# axiom_beta_interface_dummy_v0_13_r1_2.net
KiCad netlist of a schematic drawn in EAGLE
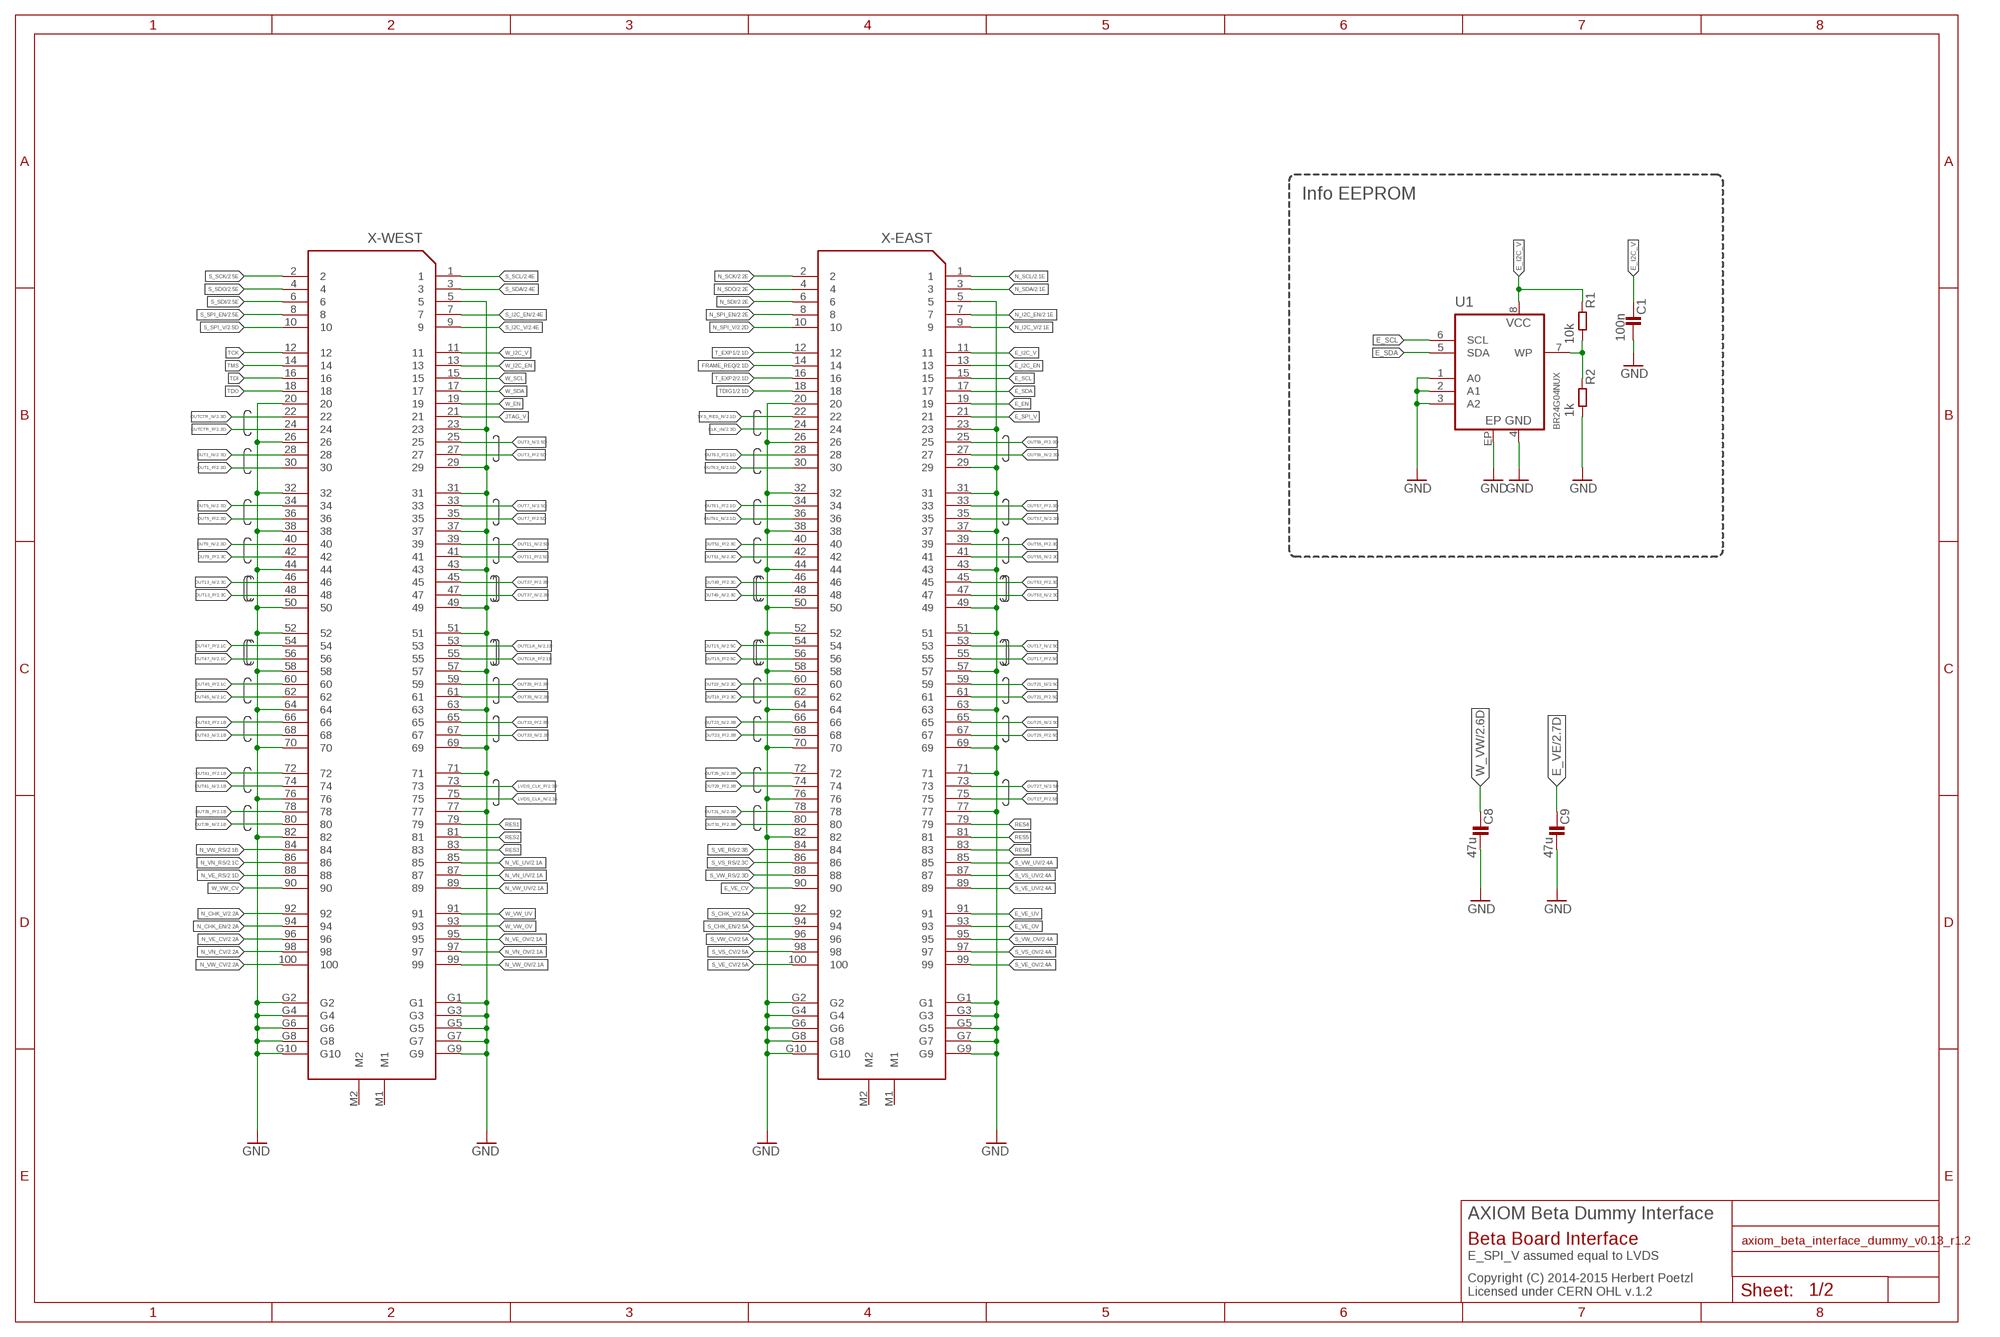
[diagram p0: schematic, sheet 1]
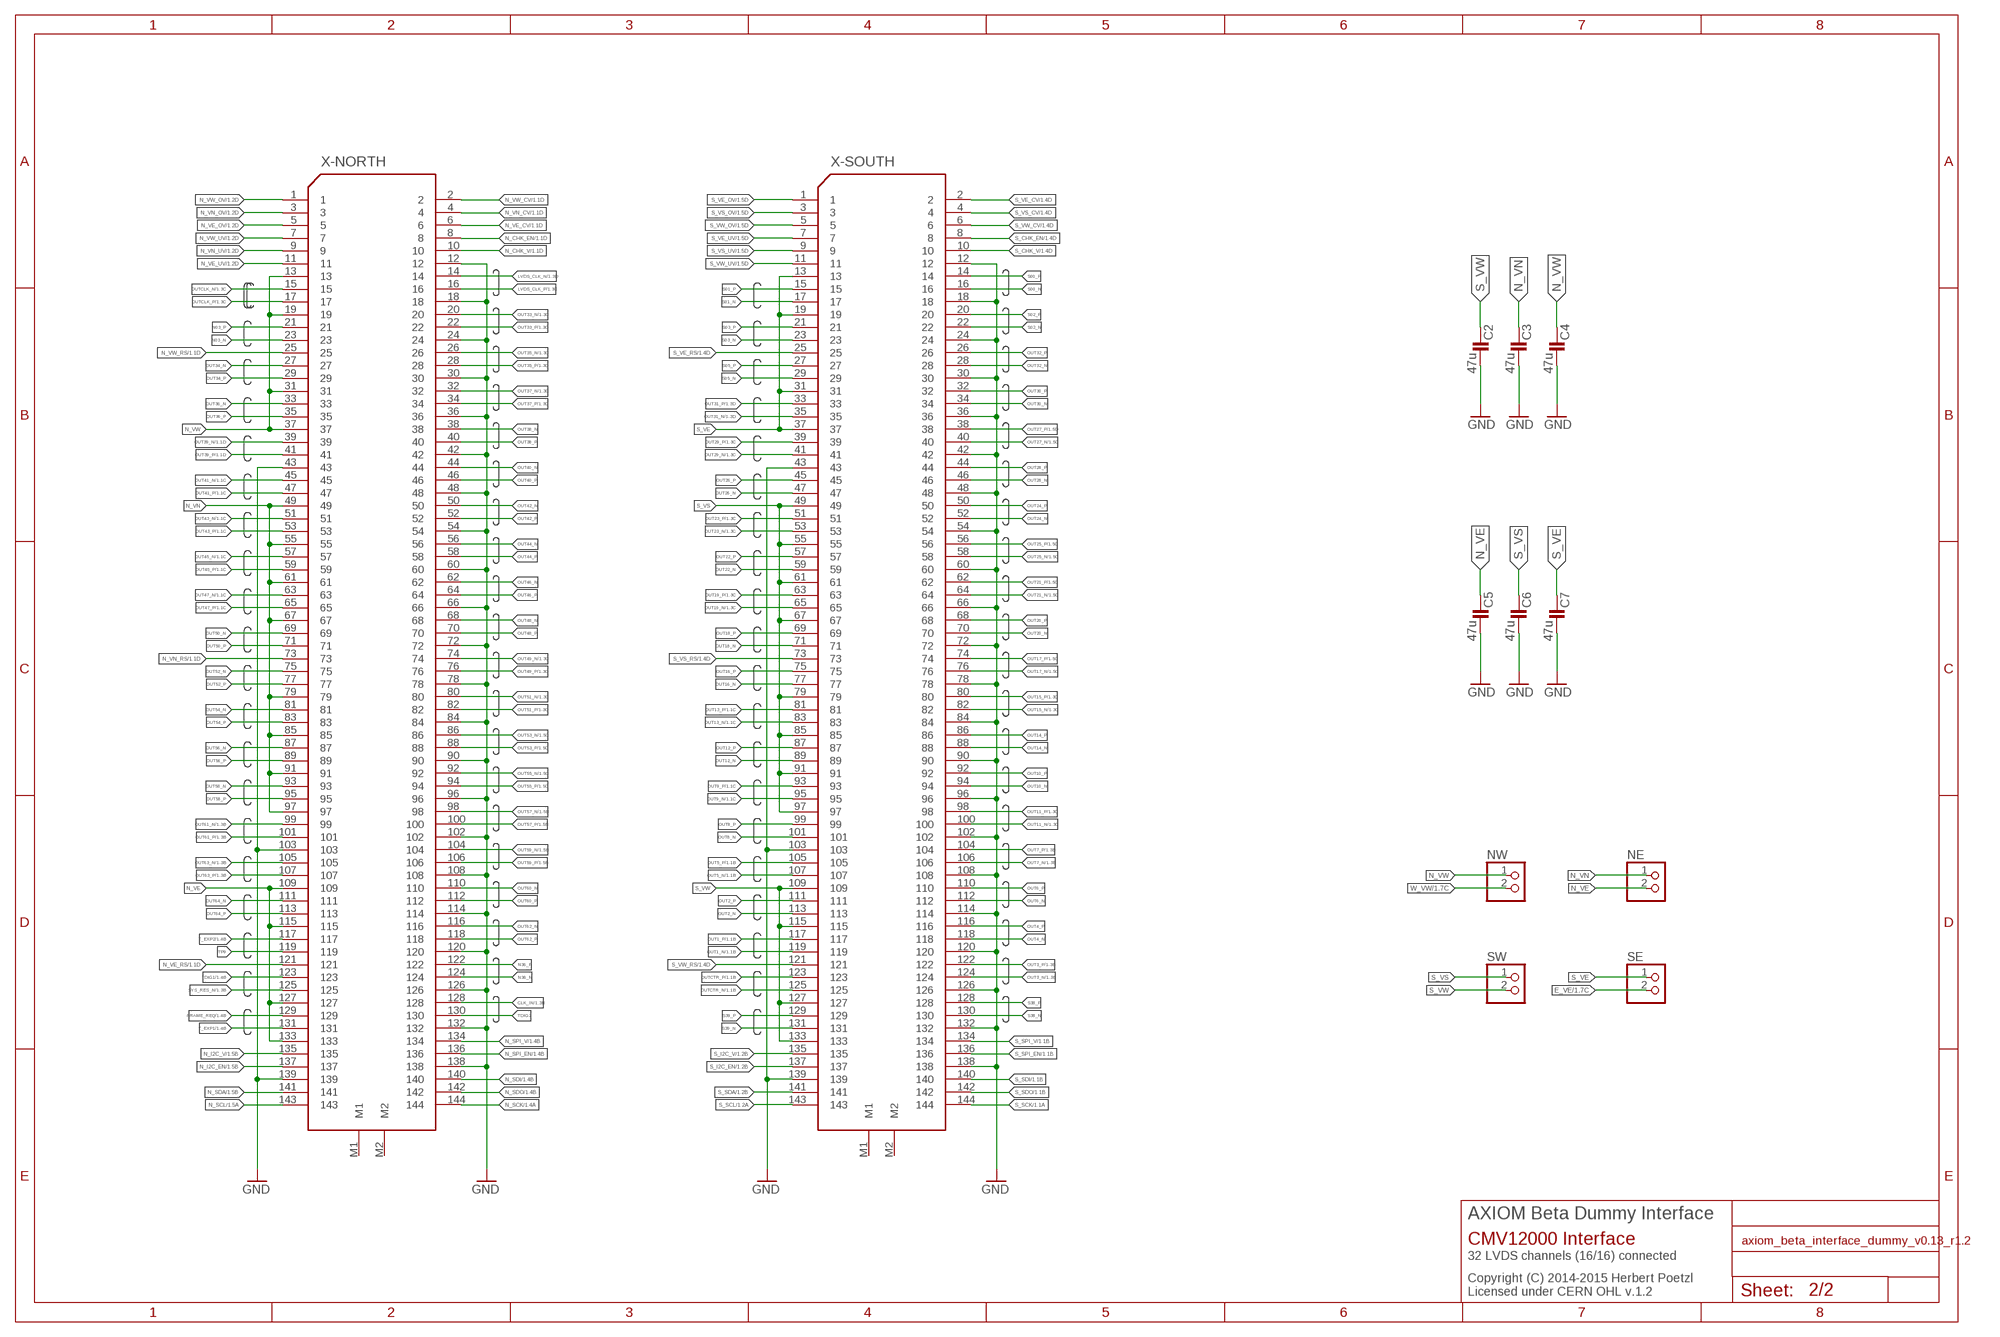
[diagram p1: schematic, sheet 2]

(export (version "E")
  (design (tool "Eeschema 10.0.6"))
  (components
    (comp (ref "C1")
      (value "100n")
      (footprint "eagle-import:0402-B")
      (libsource (lib "eagle-import") (part "C0402-B"))
    )
    (comp (ref "C8")
      (value "47u")
      (footprint "eagle-import:0805-B")
      (libsource (lib "eagle-import") (part "C0805-B"))
    )
    (comp (ref "C9")
      (value "47u")
      (footprint "eagle-import:0805-B")
      (libsource (lib "eagle-import") (part "C0805-B"))
    )
    (comp (ref "R1")
      (value "10k")
      (footprint "eagle-import:0402-B")
      (libsource (lib "eagle-import") (part "R0402-B"))
    )
    (comp (ref "R2")
      (value "1k")
      (footprint "eagle-import:0402-B")
      (libsource (lib "eagle-import") (part "R0402-B"))
    )
    (comp (ref "U1")
      (value "BR24G04NUX")
      (footprint "eagle-import:DFN200X300X100-9N")
      (libsource (lib "eagle-import") (part "BR24G04NUX"))
    )
    (comp (ref "X-EAST")
      (value "FX10-100/10P")
      (footprint "eagle-import:FX10A-100P_10")
      (libsource (lib "eagle-import") (part "FX10-100/10P"))
    )
    (comp (ref "X-WEST")
      (value "FX10-100/10P")
      (footprint "eagle-import:FX10A-100P_10")
      (libsource (lib "eagle-import") (part "FX10-100/10P"))
    )
    (comp (ref "C2")
      (value "47u")
      (footprint "eagle-import:0805-B")
      (libsource (lib "eagle-import") (part "C0805-B"))
    )
    (comp (ref "C3")
      (value "47u")
      (footprint "eagle-import:0805-B")
      (libsource (lib "eagle-import") (part "C0805-B"))
    )
    (comp (ref "C4")
      (value "47u")
      (footprint "eagle-import:0805-B")
      (libsource (lib "eagle-import") (part "C0805-B"))
    )
    (comp (ref "C5")
      (value "47u")
      (footprint "eagle-import:0805-B")
      (libsource (lib "eagle-import") (part "C0805-B"))
    )
    (comp (ref "C6")
      (value "47u")
      (footprint "eagle-import:0805-B")
      (libsource (lib "eagle-import") (part "C0805-B"))
    )
    (comp (ref "C7")
      (value "47u")
      (footprint "eagle-import:0805-B")
      (libsource (lib "eagle-import") (part "C0805-B"))
    )
    (comp (ref "NE")
      (value "PINHD-1X02_2.54")
      (footprint "eagle-import:1X02")
      (libsource (lib "eagle-import") (part "PINHD-1X02_2.54"))
    )
    (comp (ref "NW")
      (value "PINHD-1X02_2.54")
      (footprint "eagle-import:1X02")
      (libsource (lib "eagle-import") (part "PINHD-1X02_2.54"))
    )
    (comp (ref "SE")
      (value "PINHD-1X02_2.54")
      (footprint "eagle-import:1X02")
      (libsource (lib "eagle-import") (part "PINHD-1X02_2.54"))
    )
    (comp (ref "SW")
      (value "PINHD-1X02_2.54")
      (footprint "eagle-import:1X02")
      (libsource (lib "eagle-import") (part "PINHD-1X02_2.54"))
    )
    (comp (ref "X-NORTH")
      (value "FX10-144S")
      (footprint "eagle-import:FX10A-144S")
      (libsource (lib "eagle-import") (part "FX10-144S"))
    )
    (comp (ref "X-SOUTH")
      (value "FX10-144S")
      (footprint "eagle-import:FX10A-144S")
      (libsource (lib "eagle-import") (part "FX10-144S"))
    )
  )
  (nets
    (net (code "1") (name "CLK_IN") (class "Default")
      (node (ref "X-EAST") (pin "24") (pinfunction "24_24") (pintype "bidirectional"))
      (node (ref "X-NORTH") (pin "128") (pinfunction "128_128") (pintype "bidirectional"))
    )
    (net (code "2") (name "E_EN") (class "Default")
      (node (ref "X-EAST") (pin "19") (pinfunction "19_19") (pintype "bidirectional"))
    )
    (net (code "3") (name "E_I2C_EN") (class "Default")
      (node (ref "X-EAST") (pin "13") (pinfunction "13_13") (pintype "bidirectional"))
    )
    (net (code "4") (name "E_I2C_V") (class "Default")
      (node (ref "C1") (pin "1") (pinfunction "1_1") (pintype "passive"))
      (node (ref "R1") (pin "1") (pinfunction "1_1") (pintype "passive"))
      (node (ref "U1") (pin "8") (pinfunction "VCC_8") (pintype "power_in"))
      (node (ref "X-EAST") (pin "11") (pinfunction "11_11") (pintype "bidirectional"))
    )
    (net (code "5") (name "E_SCL") (class "Default")
      (node (ref "U1") (pin "6") (pinfunction "SCL_6") (pintype "input"))
      (node (ref "X-EAST") (pin "15") (pinfunction "15_15") (pintype "bidirectional"))
    )
    (net (code "6") (name "E_SDA") (class "Default")
      (node (ref "U1") (pin "5") (pinfunction "SDA_5") (pintype "bidirectional"))
      (node (ref "X-EAST") (pin "17") (pinfunction "17_17") (pintype "bidirectional"))
    )
    (net (code "7") (name "E_SPI_V") (class "Default")
      (node (ref "X-EAST") (pin "21") (pinfunction "21_21") (pintype "bidirectional"))
    )
    (net (code "8") (name "E_VE") (class "Default")
      (node (ref "C9") (pin "1") (pinfunction "1_1") (pintype "passive"))
      (node (ref "SE") (pin "2") (pinfunction "2_2") (pintype "passive"))
    )
    (net (code "9") (name "E_VE_CV") (class "Default")
      (node (ref "X-EAST") (pin "90") (pinfunction "90_90") (pintype "bidirectional"))
    )
    (net (code "10") (name "E_VE_OV") (class "Default")
      (node (ref "X-EAST") (pin "93") (pinfunction "93_93") (pintype "bidirectional"))
    )
    (net (code "11") (name "E_VE_UV") (class "Default")
      (node (ref "X-EAST") (pin "91") (pinfunction "91_91") (pintype "bidirectional"))
    )
    (net (code "12") (name "FRAME_REQ") (class "Default")
      (node (ref "X-EAST") (pin "14") (pinfunction "14_14") (pintype "bidirectional"))
      (node (ref "X-NORTH") (pin "129") (pinfunction "129_129") (pintype "bidirectional"))
    )
    (net (code "13") (name "GND") (class "Default")
      (node (ref "C1") (pin "2") (pinfunction "2_2") (pintype "passive"))
      (node (ref "C2") (pin "2") (pinfunction "2_2") (pintype "passive"))
      (node (ref "C3") (pin "2") (pinfunction "2_2") (pintype "passive"))
      (node (ref "C4") (pin "2") (pinfunction "2_2") (pintype "passive"))
      (node (ref "C5") (pin "2") (pinfunction "2_2") (pintype "passive"))
      (node (ref "C6") (pin "2") (pinfunction "2_2") (pintype "passive"))
      (node (ref "C7") (pin "2") (pinfunction "2_2") (pintype "passive"))
      (node (ref "C8") (pin "2") (pinfunction "2_2") (pintype "passive"))
      (node (ref "C9") (pin "2") (pinfunction "2_2") (pintype "passive"))
      (node (ref "R2") (pin "2") (pinfunction "2_2") (pintype "passive"))
      (node (ref "U1") (pin "1") (pinfunction "A0_1") (pintype "input"))
      (node (ref "U1") (pin "2") (pinfunction "A1_2") (pintype "input"))
      (node (ref "U1") (pin "3") (pinfunction "A2_3") (pintype "input"))
      (node (ref "U1") (pin "4") (pinfunction "GND_4") (pintype "passive"))
      (node (ref "U1") (pin "EP") (pinfunction "EP_EP") (pintype "passive"))
      (node (ref "X-EAST") (pin "20") (pinfunction "20_20") (pintype "bidirectional"))
      (node (ref "X-EAST") (pin "23") (pinfunction "23_23") (pintype "bidirectional"))
      (node (ref "X-EAST") (pin "26") (pinfunction "26_26") (pintype "bidirectional"))
      (node (ref "X-EAST") (pin "29") (pinfunction "29_29") (pintype "bidirectional"))
      (node (ref "X-EAST") (pin "31") (pinfunction "31_31") (pintype "bidirectional"))
      (node (ref "X-EAST") (pin "32") (pinfunction "32_32") (pintype "bidirectional"))
      (node (ref "X-EAST") (pin "37") (pinfunction "37_37") (pintype "bidirectional"))
      (node (ref "X-EAST") (pin "38") (pinfunction "38_38") (pintype "bidirectional"))
      (node (ref "X-EAST") (pin "43") (pinfunction "43_43") (pintype "bidirectional"))
      (node (ref "X-EAST") (pin "44") (pinfunction "44_44") (pintype "bidirectional"))
      (node (ref "X-EAST") (pin "49") (pinfunction "49_49") (pintype "bidirectional"))
      (node (ref "X-EAST") (pin "5") (pinfunction "5_5") (pintype "bidirectional"))
      (node (ref "X-EAST") (pin "50") (pinfunction "50_50") (pintype "bidirectional"))
      (node (ref "X-EAST") (pin "51") (pinfunction "51_51") (pintype "bidirectional"))
      (node (ref "X-EAST") (pin "52") (pinfunction "52_52") (pintype "bidirectional"))
      (node (ref "X-EAST") (pin "57") (pinfunction "57_57") (pintype "bidirectional"))
      (node (ref "X-EAST") (pin "58") (pinfunction "58_58") (pintype "bidirectional"))
      (node (ref "X-EAST") (pin "63") (pinfunction "63_63") (pintype "bidirectional"))
      (node (ref "X-EAST") (pin "64") (pinfunction "64_64") (pintype "bidirectional"))
      (node (ref "X-EAST") (pin "69") (pinfunction "69_69") (pintype "bidirectional"))
      (node (ref "X-EAST") (pin "70") (pinfunction "70_70") (pintype "bidirectional"))
      (node (ref "X-EAST") (pin "71") (pinfunction "71_71") (pintype "bidirectional"))
      (node (ref "X-EAST") (pin "76") (pinfunction "76_76") (pintype "bidirectional"))
      (node (ref "X-EAST") (pin "77") (pinfunction "77_77") (pintype "bidirectional"))
      (node (ref "X-EAST") (pin "82") (pinfunction "82_82") (pintype "bidirectional"))
      (node (ref "X-EAST") (pin "G1") (pinfunction "G1_G1") (pintype "bidirectional"))
      (node (ref "X-EAST") (pin "G10") (pinfunction "G10_G10") (pintype "bidirectional"))
      (node (ref "X-EAST") (pin "G2") (pinfunction "G2_G2") (pintype "bidirectional"))
      (node (ref "X-EAST") (pin "G3") (pinfunction "G3_G3") (pintype "bidirectional"))
      (node (ref "X-EAST") (pin "G4") (pinfunction "G4_G4") (pintype "bidirectional"))
      (node (ref "X-EAST") (pin "G5") (pinfunction "G5_G5") (pintype "bidirectional"))
      (node (ref "X-EAST") (pin "G6") (pinfunction "G6_G6") (pintype "bidirectional"))
      (node (ref "X-EAST") (pin "G7") (pinfunction "G7_G7") (pintype "bidirectional"))
      (node (ref "X-EAST") (pin "G8") (pinfunction "G8_G8") (pintype "bidirectional"))
      (node (ref "X-EAST") (pin "G9") (pinfunction "G9_G9") (pintype "bidirectional"))
      (node (ref "X-NORTH") (pin "102") (pinfunction "102_102") (pintype "bidirectional"))
      (node (ref "X-NORTH") (pin "103") (pinfunction "103_103") (pintype "bidirectional"))
      (node (ref "X-NORTH") (pin "108") (pinfunction "108_108") (pintype "bidirectional"))
      (node (ref "X-NORTH") (pin "114") (pinfunction "114_114") (pintype "bidirectional"))
      (node (ref "X-NORTH") (pin "12") (pinfunction "12_12") (pintype "bidirectional"))
      (node (ref "X-NORTH") (pin "120") (pinfunction "120_120") (pintype "bidirectional"))
      (node (ref "X-NORTH") (pin "126") (pinfunction "126_126") (pintype "bidirectional"))
      (node (ref "X-NORTH") (pin "132") (pinfunction "132_132") (pintype "bidirectional"))
      (node (ref "X-NORTH") (pin "138") (pinfunction "138_138") (pintype "bidirectional"))
      (node (ref "X-NORTH") (pin "139") (pinfunction "139_139") (pintype "bidirectional"))
      (node (ref "X-NORTH") (pin "18") (pinfunction "18_18") (pintype "bidirectional"))
      (node (ref "X-NORTH") (pin "24") (pinfunction "24_24") (pintype "bidirectional"))
      (node (ref "X-NORTH") (pin "30") (pinfunction "30_30") (pintype "bidirectional"))
      (node (ref "X-NORTH") (pin "36") (pinfunction "36_36") (pintype "bidirectional"))
      (node (ref "X-NORTH") (pin "42") (pinfunction "42_42") (pintype "bidirectional"))
      (node (ref "X-NORTH") (pin "43") (pinfunction "43_43") (pintype "bidirectional"))
      (node (ref "X-NORTH") (pin "48") (pinfunction "48_48") (pintype "bidirectional"))
      (node (ref "X-NORTH") (pin "54") (pinfunction "54_54") (pintype "bidirectional"))
      (node (ref "X-NORTH") (pin "60") (pinfunction "60_60") (pintype "bidirectional"))
      (node (ref "X-NORTH") (pin "66") (pinfunction "66_66") (pintype "bidirectional"))
      (node (ref "X-NORTH") (pin "72") (pinfunction "72_72") (pintype "bidirectional"))
      (node (ref "X-NORTH") (pin "78") (pinfunction "78_78") (pintype "bidirectional"))
      (node (ref "X-NORTH") (pin "84") (pinfunction "84_84") (pintype "bidirectional"))
      (node (ref "X-NORTH") (pin "90") (pinfunction "90_90") (pintype "bidirectional"))
      (node (ref "X-NORTH") (pin "96") (pinfunction "96_96") (pintype "bidirectional"))
      (node (ref "X-SOUTH") (pin "102") (pinfunction "102_102") (pintype "bidirectional"))
      (node (ref "X-SOUTH") (pin "103") (pinfunction "103_103") (pintype "bidirectional"))
      (node (ref "X-SOUTH") (pin "108") (pinfunction "108_108") (pintype "bidirectional"))
      (node (ref "X-SOUTH") (pin "114") (pinfunction "114_114") (pintype "bidirectional"))
      (node (ref "X-SOUTH") (pin "12") (pinfunction "12_12") (pintype "bidirectional"))
      (node (ref "X-SOUTH") (pin "120") (pinfunction "120_120") (pintype "bidirectional"))
      (node (ref "X-SOUTH") (pin "126") (pinfunction "126_126") (pintype "bidirectional"))
      (node (ref "X-SOUTH") (pin "132") (pinfunction "132_132") (pintype "bidirectional"))
      (node (ref "X-SOUTH") (pin "138") (pinfunction "138_138") (pintype "bidirectional"))
      (node (ref "X-SOUTH") (pin "139") (pinfunction "139_139") (pintype "bidirectional"))
      (node (ref "X-SOUTH") (pin "18") (pinfunction "18_18") (pintype "bidirectional"))
      (node (ref "X-SOUTH") (pin "24") (pinfunction "24_24") (pintype "bidirectional"))
      (node (ref "X-SOUTH") (pin "30") (pinfunction "30_30") (pintype "bidirectional"))
      (node (ref "X-SOUTH") (pin "36") (pinfunction "36_36") (pintype "bidirectional"))
      (node (ref "X-SOUTH") (pin "42") (pinfunction "42_42") (pintype "bidirectional"))
      (node (ref "X-SOUTH") (pin "43") (pinfunction "43_43") (pintype "bidirectional"))
      (node (ref "X-SOUTH") (pin "48") (pinfunction "48_48") (pintype "bidirectional"))
      (node (ref "X-SOUTH") (pin "54") (pinfunction "54_54") (pintype "bidirectional"))
      (node (ref "X-SOUTH") (pin "60") (pinfunction "60_60") (pintype "bidirectional"))
      (node (ref "X-SOUTH") (pin "66") (pinfunction "66_66") (pintype "bidirectional"))
      (node (ref "X-SOUTH") (pin "72") (pinfunction "72_72") (pintype "bidirectional"))
      (node (ref "X-SOUTH") (pin "78") (pinfunction "78_78") (pintype "bidirectional"))
      (node (ref "X-SOUTH") (pin "84") (pinfunction "84_84") (pintype "bidirectional"))
      (node (ref "X-SOUTH") (pin "90") (pinfunction "90_90") (pintype "bidirectional"))
      (node (ref "X-SOUTH") (pin "96") (pinfunction "96_96") (pintype "bidirectional"))
      (node (ref "X-WEST") (pin "20") (pinfunction "20_20") (pintype "bidirectional"))
      (node (ref "X-WEST") (pin "23") (pinfunction "23_23") (pintype "bidirectional"))
      (node (ref "X-WEST") (pin "26") (pinfunction "26_26") (pintype "bidirectional"))
      (node (ref "X-WEST") (pin "29") (pinfunction "29_29") (pintype "bidirectional"))
      (node (ref "X-WEST") (pin "31") (pinfunction "31_31") (pintype "bidirectional"))
      (node (ref "X-WEST") (pin "32") (pinfunction "32_32") (pintype "bidirectional"))
      (node (ref "X-WEST") (pin "37") (pinfunction "37_37") (pintype "bidirectional"))
      (node (ref "X-WEST") (pin "38") (pinfunction "38_38") (pintype "bidirectional"))
      (node (ref "X-WEST") (pin "43") (pinfunction "43_43") (pintype "bidirectional"))
      (node (ref "X-WEST") (pin "44") (pinfunction "44_44") (pintype "bidirectional"))
      (node (ref "X-WEST") (pin "49") (pinfunction "49_49") (pintype "bidirectional"))
      (node (ref "X-WEST") (pin "5") (pinfunction "5_5") (pintype "bidirectional"))
      (node (ref "X-WEST") (pin "50") (pinfunction "50_50") (pintype "bidirectional"))
      (node (ref "X-WEST") (pin "51") (pinfunction "51_51") (pintype "bidirectional"))
      (node (ref "X-WEST") (pin "52") (pinfunction "52_52") (pintype "bidirectional"))
      (node (ref "X-WEST") (pin "57") (pinfunction "57_57") (pintype "bidirectional"))
      (node (ref "X-WEST") (pin "58") (pinfunction "58_58") (pintype "bidirectional"))
      (node (ref "X-WEST") (pin "63") (pinfunction "63_63") (pintype "bidirectional"))
      (node (ref "X-WEST") (pin "64") (pinfunction "64_64") (pintype "bidirectional"))
      (node (ref "X-WEST") (pin "69") (pinfunction "69_69") (pintype "bidirectional"))
      (node (ref "X-WEST") (pin "70") (pinfunction "70_70") (pintype "bidirectional"))
      (node (ref "X-WEST") (pin "71") (pinfunction "71_71") (pintype "bidirectional"))
      (node (ref "X-WEST") (pin "76") (pinfunction "76_76") (pintype "bidirectional"))
      (node (ref "X-WEST") (pin "77") (pinfunction "77_77") (pintype "bidirectional"))
      (node (ref "X-WEST") (pin "82") (pinfunction "82_82") (pintype "bidirectional"))
      (node (ref "X-WEST") (pin "G1") (pinfunction "G1_G1") (pintype "bidirectional"))
      (node (ref "X-WEST") (pin "G10") (pinfunction "G10_G10") (pintype "bidirectional"))
      (node (ref "X-WEST") (pin "G2") (pinfunction "G2_G2") (pintype "bidirectional"))
      (node (ref "X-WEST") (pin "G3") (pinfunction "G3_G3") (pintype "bidirectional"))
      (node (ref "X-WEST") (pin "G4") (pinfunction "G4_G4") (pintype "bidirectional"))
      (node (ref "X-WEST") (pin "G5") (pinfunction "G5_G5") (pintype "bidirectional"))
      (node (ref "X-WEST") (pin "G6") (pinfunction "G6_G6") (pintype "bidirectional"))
      (node (ref "X-WEST") (pin "G7") (pinfunction "G7_G7") (pintype "bidirectional"))
      (node (ref "X-WEST") (pin "G8") (pinfunction "G8_G8") (pintype "bidirectional"))
      (node (ref "X-WEST") (pin "G9") (pinfunction "G9_G9") (pintype "bidirectional"))
    )
    (net (code "14") (name "JTAG_V") (class "Default")
      (node (ref "X-WEST") (pin "21") (pinfunction "21_21") (pintype "bidirectional"))
    )
    (net (code "15") (name "LVDS_CLK_N") (class "Default")
      (node (ref "X-NORTH") (pin "14") (pinfunction "14_14") (pintype "bidirectional"))
      (node (ref "X-WEST") (pin "75") (pinfunction "75_75") (pintype "bidirectional"))
    )
    (net (code "16") (name "LVDS_CLK_P") (class "Default")
      (node (ref "X-NORTH") (pin "16") (pinfunction "16_16") (pintype "bidirectional"))
      (node (ref "X-WEST") (pin "73") (pinfunction "73_73") (pintype "bidirectional"))
    )
    (net (code "17") (name "N03_N") (class "Default")
      (node (ref "X-NORTH") (pin "23") (pinfunction "23_23") (pintype "bidirectional"))
    )
    (net (code "18") (name "N03_P") (class "Default")
      (node (ref "X-NORTH") (pin "21") (pinfunction "21_21") (pintype "bidirectional"))
    )
    (net (code "19") (name "N36_N") (class "Default")
      (node (ref "X-NORTH") (pin "124") (pinfunction "124_124") (pintype "bidirectional"))
    )
    (net (code "20") (name "N36_P") (class "Default")
      (node (ref "X-NORTH") (pin "122") (pinfunction "122_122") (pintype "bidirectional"))
    )
    (net (code "21") (name "N_CHK_EN") (class "Default")
      (node (ref "X-NORTH") (pin "8") (pinfunction "8_8") (pintype "bidirectional"))
      (node (ref "X-WEST") (pin "94") (pinfunction "94_94") (pintype "bidirectional"))
    )
    (net (code "22") (name "N_CHK_V") (class "Default")
      (node (ref "X-NORTH") (pin "10") (pinfunction "10_10") (pintype "bidirectional"))
      (node (ref "X-WEST") (pin "92") (pinfunction "92_92") (pintype "bidirectional"))
    )
    (net (code "23") (name "N_I2C_EN") (class "Default")
      (node (ref "X-EAST") (pin "7") (pinfunction "7_7") (pintype "bidirectional"))
      (node (ref "X-NORTH") (pin "137") (pinfunction "137_137") (pintype "bidirectional"))
    )
    (net (code "24") (name "N_I2C_V") (class "Default")
      (node (ref "X-EAST") (pin "9") (pinfunction "9_9") (pintype "bidirectional"))
      (node (ref "X-NORTH") (pin "135") (pinfunction "135_135") (pintype "bidirectional"))
    )
    (net (code "25") (name "N_SCK") (class "Default")
      (node (ref "X-EAST") (pin "2") (pinfunction "2_2") (pintype "bidirectional"))
      (node (ref "X-NORTH") (pin "144") (pinfunction "144_144") (pintype "bidirectional"))
    )
    (net (code "26") (name "N_SCL") (class "Default")
      (node (ref "X-EAST") (pin "1") (pinfunction "1_1") (pintype "bidirectional"))
      (node (ref "X-NORTH") (pin "143") (pinfunction "143_143") (pintype "bidirectional"))
    )
    (net (code "27") (name "N_SDA") (class "Default")
      (node (ref "X-EAST") (pin "3") (pinfunction "3_3") (pintype "bidirectional"))
      (node (ref "X-NORTH") (pin "141") (pinfunction "141_141") (pintype "bidirectional"))
    )
    (net (code "28") (name "N_SDI") (class "Default")
      (node (ref "X-EAST") (pin "6") (pinfunction "6_6") (pintype "bidirectional"))
      (node (ref "X-NORTH") (pin "140") (pinfunction "140_140") (pintype "bidirectional"))
    )
    (net (code "29") (name "N_SDO") (class "Default")
      (node (ref "X-EAST") (pin "4") (pinfunction "4_4") (pintype "bidirectional"))
      (node (ref "X-NORTH") (pin "142") (pinfunction "142_142") (pintype "bidirectional"))
    )
    (net (code "30") (name "N_SPI_EN") (class "Default")
      (node (ref "X-EAST") (pin "8") (pinfunction "8_8") (pintype "bidirectional"))
      (node (ref "X-NORTH") (pin "136") (pinfunction "136_136") (pintype "bidirectional"))
    )
    (net (code "31") (name "N_SPI_V") (class "Default")
      (node (ref "X-EAST") (pin "10") (pinfunction "10_10") (pintype "bidirectional"))
      (node (ref "X-NORTH") (pin "134") (pinfunction "134_134") (pintype "bidirectional"))
    )
    (net (code "32") (name "N_VE") (class "Default")
      (node (ref "C5") (pin "1") (pinfunction "1_1") (pintype "passive"))
      (node (ref "NE") (pin "2") (pinfunction "2_2") (pintype "passive"))
      (node (ref "X-NORTH") (pin "109") (pinfunction "109_109") (pintype "bidirectional"))
      (node (ref "X-NORTH") (pin "115") (pinfunction "115_115") (pintype "bidirectional"))
      (node (ref "X-NORTH") (pin "127") (pinfunction "127_127") (pintype "bidirectional"))
      (node (ref "X-NORTH") (pin "133") (pinfunction "133_133") (pintype "bidirectional"))
    )
    (net (code "33") (name "N_VE_CV") (class "Default")
      (node (ref "X-NORTH") (pin "6") (pinfunction "6_6") (pintype "bidirectional"))
      (node (ref "X-WEST") (pin "96") (pinfunction "96_96") (pintype "bidirectional"))
    )
    (net (code "34") (name "N_VE_OV") (class "Default")
      (node (ref "X-NORTH") (pin "5") (pinfunction "5_5") (pintype "bidirectional"))
      (node (ref "X-WEST") (pin "95") (pinfunction "95_95") (pintype "bidirectional"))
    )
    (net (code "35") (name "N_VE_RS") (class "Default")
      (node (ref "X-NORTH") (pin "121") (pinfunction "121_121") (pintype "bidirectional"))
      (node (ref "X-WEST") (pin "88") (pinfunction "88_88") (pintype "bidirectional"))
    )
    (net (code "36") (name "N_VE_UV") (class "Default")
      (node (ref "X-NORTH") (pin "11") (pinfunction "11_11") (pintype "bidirectional"))
      (node (ref "X-WEST") (pin "85") (pinfunction "85_85") (pintype "bidirectional"))
    )
    (net (code "37") (name "N_VN") (class "Default")
      (node (ref "C3") (pin "1") (pinfunction "1_1") (pintype "passive"))
      (node (ref "NE") (pin "1") (pinfunction "1_1") (pintype "passive"))
      (node (ref "X-NORTH") (pin "49") (pinfunction "49_49") (pintype "bidirectional"))
      (node (ref "X-NORTH") (pin "55") (pinfunction "55_55") (pintype "bidirectional"))
      (node (ref "X-NORTH") (pin "61") (pinfunction "61_61") (pintype "bidirectional"))
      (node (ref "X-NORTH") (pin "67") (pinfunction "67_67") (pintype "bidirectional"))
      (node (ref "X-NORTH") (pin "79") (pinfunction "79_79") (pintype "bidirectional"))
      (node (ref "X-NORTH") (pin "85") (pinfunction "85_85") (pintype "bidirectional"))
      (node (ref "X-NORTH") (pin "91") (pinfunction "91_91") (pintype "bidirectional"))
      (node (ref "X-NORTH") (pin "97") (pinfunction "97_97") (pintype "bidirectional"))
    )
    (net (code "38") (name "N_VN_CV") (class "Default")
      (node (ref "X-NORTH") (pin "4") (pinfunction "4_4") (pintype "bidirectional"))
      (node (ref "X-WEST") (pin "98") (pinfunction "98_98") (pintype "bidirectional"))
    )
    (net (code "39") (name "N_VN_OV") (class "Default")
      (node (ref "X-NORTH") (pin "3") (pinfunction "3_3") (pintype "bidirectional"))
      (node (ref "X-WEST") (pin "97") (pinfunction "97_97") (pintype "bidirectional"))
    )
    (net (code "40") (name "N_VN_RS") (class "Default")
      (node (ref "X-NORTH") (pin "73") (pinfunction "73_73") (pintype "bidirectional"))
      (node (ref "X-WEST") (pin "86") (pinfunction "86_86") (pintype "bidirectional"))
    )
    (net (code "41") (name "N_VN_UV") (class "Default")
      (node (ref "X-NORTH") (pin "9") (pinfunction "9_9") (pintype "bidirectional"))
      (node (ref "X-WEST") (pin "87") (pinfunction "87_87") (pintype "bidirectional"))
    )
    (net (code "42") (name "N_VW") (class "Default")
      (node (ref "C4") (pin "1") (pinfunction "1_1") (pintype "passive"))
      (node (ref "NW") (pin "1") (pinfunction "1_1") (pintype "passive"))
      (node (ref "X-NORTH") (pin "13") (pinfunction "13_13") (pintype "bidirectional"))
      (node (ref "X-NORTH") (pin "19") (pinfunction "19_19") (pintype "bidirectional"))
      (node (ref "X-NORTH") (pin "31") (pinfunction "31_31") (pintype "bidirectional"))
      (node (ref "X-NORTH") (pin "37") (pinfunction "37_37") (pintype "bidirectional"))
    )
    (net (code "43") (name "N_VW_CV") (class "Default")
      (node (ref "X-NORTH") (pin "2") (pinfunction "2_2") (pintype "bidirectional"))
      (node (ref "X-WEST") (pin "100") (pinfunction "100_100") (pintype "bidirectional"))
    )
    (net (code "44") (name "N_VW_OV") (class "Default")
      (node (ref "X-NORTH") (pin "1") (pinfunction "1_1") (pintype "bidirectional"))
      (node (ref "X-WEST") (pin "99") (pinfunction "99_99") (pintype "bidirectional"))
    )
    (net (code "45") (name "N_VW_RS") (class "Default")
      (node (ref "X-NORTH") (pin "25") (pinfunction "25_25") (pintype "bidirectional"))
      (node (ref "X-WEST") (pin "84") (pinfunction "84_84") (pintype "bidirectional"))
    )
    (net (code "46") (name "N_VW_UV") (class "Default")
      (node (ref "X-NORTH") (pin "7") (pinfunction "7_7") (pintype "bidirectional"))
      (node (ref "X-WEST") (pin "89") (pinfunction "89_89") (pintype "bidirectional"))
    )
    (net (code "47") (name "Net-(U1-WP)") (class "Default")
      (node (ref "R1") (pin "2") (pinfunction "2_2") (pintype "passive"))
      (node (ref "R2") (pin "1") (pinfunction "1_1") (pintype "passive"))
      (node (ref "U1") (pin "7") (pinfunction "WP_7") (pintype "input"))
    )
    (net (code "48") (name "OUT1_N") (class "Default")
      (node (ref "X-SOUTH") (pin "119") (pinfunction "119_119") (pintype "bidirectional"))
      (node (ref "X-WEST") (pin "28") (pinfunction "28_28") (pintype "bidirectional"))
    )
    (net (code "49") (name "OUT1_P") (class "Default")
      (node (ref "X-SOUTH") (pin "117") (pinfunction "117_117") (pintype "bidirectional"))
      (node (ref "X-WEST") (pin "30") (pinfunction "30_30") (pintype "bidirectional"))
    )
    (net (code "50") (name "OUT2_N") (class "Default")
      (node (ref "X-SOUTH") (pin "113") (pinfunction "113_113") (pintype "bidirectional"))
    )
    (net (code "51") (name "OUT2_P") (class "Default")
      (node (ref "X-SOUTH") (pin "111") (pinfunction "111_111") (pintype "bidirectional"))
    )
    (net (code "52") (name "OUT3_N") (class "Default")
      (node (ref "X-SOUTH") (pin "124") (pinfunction "124_124") (pintype "bidirectional"))
      (node (ref "X-WEST") (pin "25") (pinfunction "25_25") (pintype "bidirectional"))
    )
    (net (code "53") (name "OUT3_P") (class "Default")
      (node (ref "X-SOUTH") (pin "122") (pinfunction "122_122") (pintype "bidirectional"))
      (node (ref "X-WEST") (pin "27") (pinfunction "27_27") (pintype "bidirectional"))
    )
    (net (code "54") (name "OUT4_N") (class "Default")
      (node (ref "X-SOUTH") (pin "118") (pinfunction "118_118") (pintype "bidirectional"))
    )
    (net (code "55") (name "OUT4_P") (class "Default")
      (node (ref "X-SOUTH") (pin "116") (pinfunction "116_116") (pintype "bidirectional"))
    )
    (net (code "56") (name "OUT5_N") (class "Default")
      (node (ref "X-SOUTH") (pin "107") (pinfunction "107_107") (pintype "bidirectional"))
      (node (ref "X-WEST") (pin "34") (pinfunction "34_34") (pintype "bidirectional"))
    )
    (net (code "57") (name "OUT5_P") (class "Default")
      (node (ref "X-SOUTH") (pin "105") (pinfunction "105_105") (pintype "bidirectional"))
      (node (ref "X-WEST") (pin "36") (pinfunction "36_36") (pintype "bidirectional"))
    )
    (net (code "58") (name "OUT6_N") (class "Default")
      (node (ref "X-SOUTH") (pin "112") (pinfunction "112_112") (pintype "bidirectional"))
    )
    (net (code "59") (name "OUT6_P") (class "Default")
      (node (ref "X-SOUTH") (pin "110") (pinfunction "110_110") (pintype "bidirectional"))
    )
    (net (code "60") (name "OUT7_N") (class "Default")
      (node (ref "X-SOUTH") (pin "106") (pinfunction "106_106") (pintype "bidirectional"))
      (node (ref "X-WEST") (pin "33") (pinfunction "33_33") (pintype "bidirectional"))
    )
    (net (code "61") (name "OUT7_P") (class "Default")
      (node (ref "X-SOUTH") (pin "104") (pinfunction "104_104") (pintype "bidirectional"))
      (node (ref "X-WEST") (pin "35") (pinfunction "35_35") (pintype "bidirectional"))
    )
    (net (code "62") (name "OUT8_N") (class "Default")
      (node (ref "X-SOUTH") (pin "101") (pinfunction "101_101") (pintype "bidirectional"))
    )
    (net (code "63") (name "OUT8_P") (class "Default")
      (node (ref "X-SOUTH") (pin "99") (pinfunction "99_99") (pintype "bidirectional"))
    )
    (net (code "64") (name "OUT9_N") (class "Default")
      (node (ref "X-SOUTH") (pin "95") (pinfunction "95_95") (pintype "bidirectional"))
      (node (ref "X-WEST") (pin "40") (pinfunction "40_40") (pintype "bidirectional"))
    )
    (net (code "65") (name "OUT9_P") (class "Default")
      (node (ref "X-SOUTH") (pin "93") (pinfunction "93_93") (pintype "bidirectional"))
      (node (ref "X-WEST") (pin "42") (pinfunction "42_42") (pintype "bidirectional"))
    )
    (net (code "66") (name "OUT10_N") (class "Default")
      (node (ref "X-SOUTH") (pin "94") (pinfunction "94_94") (pintype "bidirectional"))
    )
    (net (code "67") (name "OUT10_P") (class "Default")
      (node (ref "X-SOUTH") (pin "92") (pinfunction "92_92") (pintype "bidirectional"))
    )
    (net (code "68") (name "OUT11_N") (class "Default")
      (node (ref "X-SOUTH") (pin "100") (pinfunction "100_100") (pintype "bidirectional"))
      (node (ref "X-WEST") (pin "39") (pinfunction "39_39") (pintype "bidirectional"))
    )
    (net (code "69") (name "OUT11_P") (class "Default")
      (node (ref "X-SOUTH") (pin "98") (pinfunction "98_98") (pintype "bidirectional"))
      (node (ref "X-WEST") (pin "41") (pinfunction "41_41") (pintype "bidirectional"))
    )
    (net (code "70") (name "OUT12_N") (class "Default")
      (node (ref "X-SOUTH") (pin "89") (pinfunction "89_89") (pintype "bidirectional"))
    )
    (net (code "71") (name "OUT12_P") (class "Default")
      (node (ref "X-SOUTH") (pin "87") (pinfunction "87_87") (pintype "bidirectional"))
    )
    (net (code "72") (name "OUT13_N") (class "Default")
      (node (ref "X-SOUTH") (pin "83") (pinfunction "83_83") (pintype "bidirectional"))
      (node (ref "X-WEST") (pin "46") (pinfunction "46_46") (pintype "bidirectional"))
    )
    (net (code "73") (name "OUT13_P") (class "Default")
      (node (ref "X-SOUTH") (pin "81") (pinfunction "81_81") (pintype "bidirectional"))
      (node (ref "X-WEST") (pin "48") (pinfunction "48_48") (pintype "bidirectional"))
    )
    (net (code "74") (name "OUT14_N") (class "Default")
      (node (ref "X-SOUTH") (pin "88") (pinfunction "88_88") (pintype "bidirectional"))
    )
    (net (code "75") (name "OUT14_P") (class "Default")
      (node (ref "X-SOUTH") (pin "86") (pinfunction "86_86") (pintype "bidirectional"))
    )
    (net (code "76") (name "OUT15_N") (class "Default")
      (node (ref "X-EAST") (pin "54") (pinfunction "54_54") (pintype "bidirectional"))
      (node (ref "X-SOUTH") (pin "82") (pinfunction "82_82") (pintype "bidirectional"))
    )
    (net (code "77") (name "OUT15_P") (class "Default")
      (node (ref "X-EAST") (pin "56") (pinfunction "56_56") (pintype "bidirectional"))
      (node (ref "X-SOUTH") (pin "80") (pinfunction "80_80") (pintype "bidirectional"))
    )
    (net (code "78") (name "OUT16_N") (class "Default")
      (node (ref "X-SOUTH") (pin "77") (pinfunction "77_77") (pintype "bidirectional"))
    )
    (net (code "79") (name "OUT16_P") (class "Default")
      (node (ref "X-SOUTH") (pin "75") (pinfunction "75_75") (pintype "bidirectional"))
    )
    (net (code "80") (name "OUT17_N") (class "Default")
      (node (ref "X-EAST") (pin "53") (pinfunction "53_53") (pintype "bidirectional"))
      (node (ref "X-SOUTH") (pin "76") (pinfunction "76_76") (pintype "bidirectional"))
    )
    (net (code "81") (name "OUT17_P") (class "Default")
      (node (ref "X-EAST") (pin "55") (pinfunction "55_55") (pintype "bidirectional"))
      (node (ref "X-SOUTH") (pin "74") (pinfunction "74_74") (pintype "bidirectional"))
    )
    (net (code "82") (name "OUT18_N") (class "Default")
      (node (ref "X-SOUTH") (pin "71") (pinfunction "71_71") (pintype "bidirectional"))
    )
    (net (code "83") (name "OUT18_P") (class "Default")
      (node (ref "X-SOUTH") (pin "69") (pinfunction "69_69") (pintype "bidirectional"))
    )
    (net (code "84") (name "OUT19_N") (class "Default")
      (node (ref "X-EAST") (pin "60") (pinfunction "60_60") (pintype "bidirectional"))
      (node (ref "X-SOUTH") (pin "65") (pinfunction "65_65") (pintype "bidirectional"))
    )
    (net (code "85") (name "OUT19_P") (class "Default")
      (node (ref "X-EAST") (pin "62") (pinfunction "62_62") (pintype "bidirectional"))
      (node (ref "X-SOUTH") (pin "63") (pinfunction "63_63") (pintype "bidirectional"))
    )
    (net (code "86") (name "OUT20_N") (class "Default")
      (node (ref "X-SOUTH") (pin "70") (pinfunction "70_70") (pintype "bidirectional"))
    )
    (net (code "87") (name "OUT20_P") (class "Default")
      (node (ref "X-SOUTH") (pin "68") (pinfunction "68_68") (pintype "bidirectional"))
    )
    (net (code "88") (name "OUT21_N") (class "Default")
      (node (ref "X-EAST") (pin "59") (pinfunction "59_59") (pintype "bidirectional"))
      (node (ref "X-SOUTH") (pin "64") (pinfunction "64_64") (pintype "bidirectional"))
    )
    (net (code "89") (name "OUT21_P") (class "Default")
      (node (ref "X-EAST") (pin "61") (pinfunction "61_61") (pintype "bidirectional"))
      (node (ref "X-SOUTH") (pin "62") (pinfunction "62_62") (pintype "bidirectional"))
    )
    (net (code "90") (name "OUT22_N") (class "Default")
      (node (ref "X-SOUTH") (pin "59") (pinfunction "59_59") (pintype "bidirectional"))
    )
    (net (code "91") (name "OUT22_P") (class "Default")
      (node (ref "X-SOUTH") (pin "57") (pinfunction "57_57") (pintype "bidirectional"))
    )
    (net (code "92") (name "OUT23_N") (class "Default")
      (node (ref "X-EAST") (pin "66") (pinfunction "66_66") (pintype "bidirectional"))
      (node (ref "X-SOUTH") (pin "53") (pinfunction "53_53") (pintype "bidirectional"))
    )
    (net (code "93") (name "OUT23_P") (class "Default")
      (node (ref "X-EAST") (pin "68") (pinfunction "68_68") (pintype "bidirectional"))
      (node (ref "X-SOUTH") (pin "51") (pinfunction "51_51") (pintype "bidirectional"))
    )
    (net (code "94") (name "OUT24_N") (class "Default")
      (node (ref "X-SOUTH") (pin "52") (pinfunction "52_52") (pintype "bidirectional"))
    )
    (net (code "95") (name "OUT24_P") (class "Default")
      (node (ref "X-SOUTH") (pin "50") (pinfunction "50_50") (pintype "bidirectional"))
    )
    (net (code "96") (name "OUT25_N") (class "Default")
      (node (ref "X-EAST") (pin "65") (pinfunction "65_65") (pintype "bidirectional"))
      (node (ref "X-SOUTH") (pin "58") (pinfunction "58_58") (pintype "bidirectional"))
    )
    (net (code "97") (name "OUT25_P") (class "Default")
      (node (ref "X-EAST") (pin "67") (pinfunction "67_67") (pintype "bidirectional"))
      (node (ref "X-SOUTH") (pin "56") (pinfunction "56_56") (pintype "bidirectional"))
    )
    (net (code "98") (name "OUT26_N") (class "Default")
      (node (ref "X-SOUTH") (pin "47") (pinfunction "47_47") (pintype "bidirectional"))
    )
    (net (code "99") (name "OUT26_P") (class "Default")
      (node (ref "X-SOUTH") (pin "45") (pinfunction "45_45") (pintype "bidirectional"))
    )
    (net (code "100") (name "OUT27_N") (class "Default")
      (node (ref "X-EAST") (pin "73") (pinfunction "73_73") (pintype "bidirectional"))
      (node (ref "X-SOUTH") (pin "40") (pinfunction "40_40") (pintype "bidirectional"))
    )
    (net (code "101") (name "OUT27_P") (class "Default")
      (node (ref "X-EAST") (pin "75") (pinfunction "75_75") (pintype "bidirectional"))
      (node (ref "X-SOUTH") (pin "38") (pinfunction "38_38") (pintype "bidirectional"))
    )
    (net (code "102") (name "OUT28_N") (class "Default")
      (node (ref "X-SOUTH") (pin "46") (pinfunction "46_46") (pintype "bidirectional"))
    )
    (net (code "103") (name "OUT28_P") (class "Default")
      (node (ref "X-SOUTH") (pin "44") (pinfunction "44_44") (pintype "bidirectional"))
    )
    (net (code "104") (name "OUT29_N") (class "Default")
      (node (ref "X-EAST") (pin "72") (pinfunction "72_72") (pintype "bidirectional"))
      (node (ref "X-SOUTH") (pin "41") (pinfunction "41_41") (pintype "bidirectional"))
    )
    (net (code "105") (name "OUT29_P") (class "Default")
      (node (ref "X-EAST") (pin "74") (pinfunction "74_74") (pintype "bidirectional"))
      (node (ref "X-SOUTH") (pin "39") (pinfunction "39_39") (pintype "bidirectional"))
    )
    (net (code "106") (name "OUT30_N") (class "Default")
      (node (ref "X-SOUTH") (pin "34") (pinfunction "34_34") (pintype "bidirectional"))
    )
    (net (code "107") (name "OUT30_P") (class "Default")
      (node (ref "X-SOUTH") (pin "32") (pinfunction "32_32") (pintype "bidirectional"))
    )
    (net (code "108") (name "OUT31_N") (class "Default")
      (node (ref "X-EAST") (pin "78") (pinfunction "78_78") (pintype "bidirectional"))
      (node (ref "X-SOUTH") (pin "35") (pinfunction "35_35") (pintype "bidirectional"))
    )
    (net (code "109") (name "OUT31_P") (class "Default")
      (node (ref "X-EAST") (pin "80") (pinfunction "80_80") (pintype "bidirectional"))
      (node (ref "X-SOUTH") (pin "33") (pinfunction "33_33") (pintype "bidirectional"))
    )
    (net (code "110") (name "OUT32_N") (class "Default")
      (node (ref "X-SOUTH") (pin "28") (pinfunction "28_28") (pintype "bidirectional"))
    )
    (net (code "111") (name "OUT32_P") (class "Default")
      (node (ref "X-SOUTH") (pin "26") (pinfunction "26_26") (pintype "bidirectional"))
    )
    (net (code "112") (name "OUT33_N") (class "Default")
      (node (ref "X-NORTH") (pin "20") (pinfunction "20_20") (pintype "bidirectional"))
      (node (ref "X-WEST") (pin "67") (pinfunction "67_67") (pintype "bidirectional"))
    )
    (net (code "113") (name "OUT33_P") (class "Default")
      (node (ref "X-NORTH") (pin "22") (pinfunction "22_22") (pintype "bidirectional"))
      (node (ref "X-WEST") (pin "65") (pinfunction "65_65") (pintype "bidirectional"))
    )
    (net (code "114") (name "OUT34_N") (class "Default")
      (node (ref "X-NORTH") (pin "27") (pinfunction "27_27") (pintype "bidirectional"))
    )
    (net (code "115") (name "OUT34_P") (class "Default")
      (node (ref "X-NORTH") (pin "29") (pinfunction "29_29") (pintype "bidirectional"))
    )
    (net (code "116") (name "OUT35_N") (class "Default")
      (node (ref "X-NORTH") (pin "26") (pinfunction "26_26") (pintype "bidirectional"))
      (node (ref "X-WEST") (pin "61") (pinfunction "61_61") (pintype "bidirectional"))
    )
    (net (code "117") (name "OUT35_P") (class "Default")
      (node (ref "X-NORTH") (pin "28") (pinfunction "28_28") (pintype "bidirectional"))
      (node (ref "X-WEST") (pin "59") (pinfunction "59_59") (pintype "bidirectional"))
    )
    (net (code "118") (name "OUT36_N") (class "Default")
      (node (ref "X-NORTH") (pin "33") (pinfunction "33_33") (pintype "bidirectional"))
    )
    (net (code "119") (name "OUT36_P") (class "Default")
      (node (ref "X-NORTH") (pin "35") (pinfunction "35_35") (pintype "bidirectional"))
    )
    (net (code "120") (name "OUT37_N") (class "Default")
      (node (ref "X-NORTH") (pin "32") (pinfunction "32_32") (pintype "bidirectional"))
      (node (ref "X-WEST") (pin "47") (pinfunction "47_47") (pintype "bidirectional"))
    )
    (net (code "121") (name "OUT37_P") (class "Default")
      (node (ref "X-NORTH") (pin "34") (pinfunction "34_34") (pintype "bidirectional"))
      (node (ref "X-WEST") (pin "45") (pinfunction "45_45") (pintype "bidirectional"))
    )
    (net (code "122") (name "OUT38_N") (class "Default")
      (node (ref "X-NORTH") (pin "38") (pinfunction "38_38") (pintype "bidirectional"))
    )
    (net (code "123") (name "OUT38_P") (class "Default")
      (node (ref "X-NORTH") (pin "40") (pinfunction "40_40") (pintype "bidirectional"))
    )
    (net (code "124") (name "OUT39_N") (class "Default")
      (node (ref "X-NORTH") (pin "39") (pinfunction "39_39") (pintype "bidirectional"))
      (node (ref "X-WEST") (pin "80") (pinfunction "80_80") (pintype "bidirectional"))
    )
    (net (code "125") (name "OUT39_P") (class "Default")
      (node (ref "X-NORTH") (pin "41") (pinfunction "41_41") (pintype "bidirectional"))
      (node (ref "X-WEST") (pin "78") (pinfunction "78_78") (pintype "bidirectional"))
    )
    (net (code "126") (name "OUT40_N") (class "Default")
      (node (ref "X-NORTH") (pin "44") (pinfunction "44_44") (pintype "bidirectional"))
    )
    (net (code "127") (name "OUT40_P") (class "Default")
      (node (ref "X-NORTH") (pin "46") (pinfunction "46_46") (pintype "bidirectional"))
    )
    (net (code "128") (name "OUT41_N") (class "Default")
      (node (ref "X-NORTH") (pin "45") (pinfunction "45_45") (pintype "bidirectional"))
      (node (ref "X-WEST") (pin "74") (pinfunction "74_74") (pintype "bidirectional"))
    )
    (net (code "129") (name "OUT41_P") (class "Default")
      (node (ref "X-NORTH") (pin "47") (pinfunction "47_47") (pintype "bidirectional"))
      (node (ref "X-WEST") (pin "72") (pinfunction "72_72") (pintype "bidirectional"))
    )
    (net (code "130") (name "OUT42_N") (class "Default")
      (node (ref "X-NORTH") (pin "50") (pinfunction "50_50") (pintype "bidirectional"))
    )
    (net (code "131") (name "OUT42_P") (class "Default")
      (node (ref "X-NORTH") (pin "52") (pinfunction "52_52") (pintype "bidirectional"))
    )
    (net (code "132") (name "OUT43_N") (class "Default")
      (node (ref "X-NORTH") (pin "51") (pinfunction "51_51") (pintype "bidirectional"))
      (node (ref "X-WEST") (pin "68") (pinfunction "68_68") (pintype "bidirectional"))
    )
    (net (code "133") (name "OUT43_P") (class "Default")
      (node (ref "X-NORTH") (pin "53") (pinfunction "53_53") (pintype "bidirectional"))
      (node (ref "X-WEST") (pin "66") (pinfunction "66_66") (pintype "bidirectional"))
    )
    (net (code "134") (name "OUT44_N") (class "Default")
      (node (ref "X-NORTH") (pin "56") (pinfunction "56_56") (pintype "bidirectional"))
    )
    (net (code "135") (name "OUT44_P") (class "Default")
      (node (ref "X-NORTH") (pin "58") (pinfunction "58_58") (pintype "bidirectional"))
    )
    (net (code "136") (name "OUT45_N") (class "Default")
      (node (ref "X-NORTH") (pin "57") (pinfunction "57_57") (pintype "bidirectional"))
      (node (ref "X-WEST") (pin "62") (pinfunction "62_62") (pintype "bidirectional"))
    )
    (net (code "137") (name "OUT45_P") (class "Default")
      (node (ref "X-NORTH") (pin "59") (pinfunction "59_59") (pintype "bidirectional"))
      (node (ref "X-WEST") (pin "60") (pinfunction "60_60") (pintype "bidirectional"))
    )
    (net (code "138") (name "OUT46_N") (class "Default")
      (node (ref "X-NORTH") (pin "62") (pinfunction "62_62") (pintype "bidirectional"))
    )
    (net (code "139") (name "OUT46_P") (class "Default")
      (node (ref "X-NORTH") (pin "64") (pinfunction "64_64") (pintype "bidirectional"))
    )
    (net (code "140") (name "OUT47_N") (class "Default")
      (node (ref "X-NORTH") (pin "63") (pinfunction "63_63") (pintype "bidirectional"))
      (node (ref "X-WEST") (pin "56") (pinfunction "56_56") (pintype "bidirectional"))
    )
    (net (code "141") (name "OUT47_P") (class "Default")
      (node (ref "X-NORTH") (pin "65") (pinfunction "65_65") (pintype "bidirectional"))
      (node (ref "X-WEST") (pin "54") (pinfunction "54_54") (pintype "bidirectional"))
    )
    (net (code "142") (name "OUT48_N") (class "Default")
      (node (ref "X-NORTH") (pin "68") (pinfunction "68_68") (pintype "bidirectional"))
    )
    (net (code "143") (name "OUT48_P") (class "Default")
      (node (ref "X-NORTH") (pin "70") (pinfunction "70_70") (pintype "bidirectional"))
    )
    (net (code "144") (name "OUT49_N") (class "Default")
      (node (ref "X-EAST") (pin "48") (pinfunction "48_48") (pintype "bidirectional"))
      (node (ref "X-NORTH") (pin "74") (pinfunction "74_74") (pintype "bidirectional"))
    )
    (net (code "145") (name "OUT49_P") (class "Default")
      (node (ref "X-EAST") (pin "46") (pinfunction "46_46") (pintype "bidirectional"))
      (node (ref "X-NORTH") (pin "76") (pinfunction "76_76") (pintype "bidirectional"))
    )
    (net (code "146") (name "OUT50_N") (class "Default")
      (node (ref "X-NORTH") (pin "69") (pinfunction "69_69") (pintype "bidirectional"))
    )
    (net (code "147") (name "OUT50_P") (class "Default")
      (node (ref "X-NORTH") (pin "71") (pinfunction "71_71") (pintype "bidirectional"))
    )
    (net (code "148") (name "OUT51_N") (class "Default")
      (node (ref "X-EAST") (pin "42") (pinfunction "42_42") (pintype "bidirectional"))
      (node (ref "X-NORTH") (pin "80") (pinfunction "80_80") (pintype "bidirectional"))
    )
    (net (code "149") (name "OUT51_P") (class "Default")
      (node (ref "X-EAST") (pin "40") (pinfunction "40_40") (pintype "bidirectional"))
      (node (ref "X-NORTH") (pin "82") (pinfunction "82_82") (pintype "bidirectional"))
    )
    (net (code "150") (name "OUT52_N") (class "Default")
      (node (ref "X-NORTH") (pin "75") (pinfunction "75_75") (pintype "bidirectional"))
    )
    (net (code "151") (name "OUT52_P") (class "Default")
      (node (ref "X-NORTH") (pin "77") (pinfunction "77_77") (pintype "bidirectional"))
    )
    (net (code "152") (name "OUT53_N") (class "Default")
      (node (ref "X-EAST") (pin "47") (pinfunction "47_47") (pintype "bidirectional"))
      (node (ref "X-NORTH") (pin "86") (pinfunction "86_86") (pintype "bidirectional"))
    )
    (net (code "153") (name "OUT53_P") (class "Default")
      (node (ref "X-EAST") (pin "45") (pinfunction "45_45") (pintype "bidirectional"))
      (node (ref "X-NORTH") (pin "88") (pinfunction "88_88") (pintype "bidirectional"))
    )
    (net (code "154") (name "OUT54_N") (class "Default")
      (node (ref "X-NORTH") (pin "81") (pinfunction "81_81") (pintype "bidirectional"))
    )
    (net (code "155") (name "OUT54_P") (class "Default")
      (node (ref "X-NORTH") (pin "83") (pinfunction "83_83") (pintype "bidirectional"))
    )
    (net (code "156") (name "OUT55_N") (class "Default")
      (node (ref "X-EAST") (pin "41") (pinfunction "41_41") (pintype "bidirectional"))
      (node (ref "X-NORTH") (pin "92") (pinfunction "92_92") (pintype "bidirectional"))
    )
    (net (code "157") (name "OUT55_P") (class "Default")
      (node (ref "X-EAST") (pin "39") (pinfunction "39_39") (pintype "bidirectional"))
      (node (ref "X-NORTH") (pin "94") (pinfunction "94_94") (pintype "bidirectional"))
    )
    (net (code "158") (name "OUT56_N") (class "Default")
      (node (ref "X-NORTH") (pin "87") (pinfunction "87_87") (pintype "bidirectional"))
    )
    (net (code "159") (name "OUT56_P") (class "Default")
      (node (ref "X-NORTH") (pin "89") (pinfunction "89_89") (pintype "bidirectional"))
    )
    (net (code "160") (name "OUT57_N") (class "Default")
      (node (ref "X-EAST") (pin "35") (pinfunction "35_35") (pintype "bidirectional"))
      (node (ref "X-NORTH") (pin "98") (pinfunction "98_98") (pintype "bidirectional"))
    )
    (net (code "161") (name "OUT57_P") (class "Default")
      (node (ref "X-EAST") (pin "33") (pinfunction "33_33") (pintype "bidirectional"))
      (node (ref "X-NORTH") (pin "100") (pinfunction "100_100") (pintype "bidirectional"))
    )
    (net (code "162") (name "OUT58_N") (class "Default")
      (node (ref "X-NORTH") (pin "93") (pinfunction "93_93") (pintype "bidirectional"))
    )
    (net (code "163") (name "OUT58_P") (class "Default")
      (node (ref "X-NORTH") (pin "95") (pinfunction "95_95") (pintype "bidirectional"))
    )
    (net (code "164") (name "OUT59_N") (class "Default")
      (node (ref "X-EAST") (pin "27") (pinfunction "27_27") (pintype "bidirectional"))
      (node (ref "X-NORTH") (pin "104") (pinfunction "104_104") (pintype "bidirectional"))
    )
    (net (code "165") (name "OUT59_P") (class "Default")
      (node (ref "X-EAST") (pin "25") (pinfunction "25_25") (pintype "bidirectional"))
      (node (ref "X-NORTH") (pin "106") (pinfunction "106_106") (pintype "bidirectional"))
    )
    (net (code "166") (name "OUT60_N") (class "Default")
      (node (ref "X-NORTH") (pin "110") (pinfunction "110_110") (pintype "bidirectional"))
    )
    (net (code "167") (name "OUT60_P") (class "Default")
      (node (ref "X-NORTH") (pin "112") (pinfunction "112_112") (pintype "bidirectional"))
    )
    (net (code "168") (name "OUT61_N") (class "Default")
      (node (ref "X-EAST") (pin "36") (pinfunction "36_36") (pintype "bidirectional"))
      (node (ref "X-NORTH") (pin "99") (pinfunction "99_99") (pintype "bidirectional"))
    )
    (net (code "169") (name "OUT61_P") (class "Default")
      (node (ref "X-EAST") (pin "34") (pinfunction "34_34") (pintype "bidirectional"))
      (node (ref "X-NORTH") (pin "101") (pinfunction "101_101") (pintype "bidirectional"))
    )
    (net (code "170") (name "OUT62_N") (class "Default")
      (node (ref "X-NORTH") (pin "116") (pinfunction "116_116") (pintype "bidirectional"))
    )
    (net (code "171") (name "OUT62_P") (class "Default")
      (node (ref "X-NORTH") (pin "118") (pinfunction "118_118") (pintype "bidirectional"))
    )
    (net (code "172") (name "OUT63_N") (class "Default")
      (node (ref "X-EAST") (pin "30") (pinfunction "30_30") (pintype "bidirectional"))
      (node (ref "X-NORTH") (pin "105") (pinfunction "105_105") (pintype "bidirectional"))
    )
    (net (code "173") (name "OUT63_P") (class "Default")
      (node (ref "X-EAST") (pin "28") (pinfunction "28_28") (pintype "bidirectional"))
      (node (ref "X-NORTH") (pin "107") (pinfunction "107_107") (pintype "bidirectional"))
    )
    (net (code "174") (name "OUT64_N") (class "Default")
      (node (ref "X-NORTH") (pin "111") (pinfunction "111_111") (pintype "bidirectional"))
    )
    (net (code "175") (name "OUT64_P") (class "Default")
      (node (ref "X-NORTH") (pin "113") (pinfunction "113_113") (pintype "bidirectional"))
    )
    (net (code "176") (name "OUTCLK_N") (class "Default")
      (node (ref "X-NORTH") (pin "15") (pinfunction "15_15") (pintype "bidirectional"))
      (node (ref "X-WEST") (pin "53") (pinfunction "53_53") (pintype "bidirectional"))
    )
    (net (code "177") (name "OUTCLK_P") (class "Default")
      (node (ref "X-NORTH") (pin "17") (pinfunction "17_17") (pintype "bidirectional"))
      (node (ref "X-WEST") (pin "55") (pinfunction "55_55") (pintype "bidirectional"))
    )
    (net (code "178") (name "OUTCTR_N") (class "Default")
      (node (ref "X-SOUTH") (pin "125") (pinfunction "125_125") (pintype "bidirectional"))
      (node (ref "X-WEST") (pin "22") (pinfunction "22_22") (pintype "bidirectional"))
    )
    (net (code "179") (name "OUTCTR_P") (class "Default")
      (node (ref "X-SOUTH") (pin "123") (pinfunction "123_123") (pintype "bidirectional"))
      (node (ref "X-WEST") (pin "24") (pinfunction "24_24") (pintype "bidirectional"))
    )
    (net (code "180") (name "RES1") (class "Default")
      (node (ref "X-WEST") (pin "79") (pinfunction "79_79") (pintype "bidirectional"))
    )
    (net (code "181") (name "RES2") (class "Default")
      (node (ref "X-WEST") (pin "81") (pinfunction "81_81") (pintype "bidirectional"))
    )
    (net (code "182") (name "RES3") (class "Default")
      (node (ref "X-WEST") (pin "83") (pinfunction "83_83") (pintype "bidirectional"))
    )
    (net (code "183") (name "RES4") (class "Default")
      (node (ref "X-EAST") (pin "79") (pinfunction "79_79") (pintype "bidirectional"))
    )
    (net (code "184") (name "RES5") (class "Default")
      (node (ref "X-EAST") (pin "81") (pinfunction "81_81") (pintype "bidirectional"))
    )
    (net (code "185") (name "RES6") (class "Default")
      (node (ref "X-EAST") (pin "83") (pinfunction "83_83") (pintype "bidirectional"))
    )
    (net (code "186") (name "S00_N") (class "Default")
      (node (ref "X-SOUTH") (pin "16") (pinfunction "16_16") (pintype "bidirectional"))
    )
    (net (code "187") (name "S00_P") (class "Default")
      (node (ref "X-SOUTH") (pin "14") (pinfunction "14_14") (pintype "bidirectional"))
    )
    (net (code "188") (name "S01_N") (class "Default")
      (node (ref "X-SOUTH") (pin "17") (pinfunction "17_17") (pintype "bidirectional"))
    )
    (net (code "189") (name "S01_P") (class "Default")
      (node (ref "X-SOUTH") (pin "15") (pinfunction "15_15") (pintype "bidirectional"))
    )
    (net (code "190") (name "S02_N") (class "Default")
      (node (ref "X-SOUTH") (pin "22") (pinfunction "22_22") (pintype "bidirectional"))
    )
    (net (code "191") (name "S02_P") (class "Default")
      (node (ref "X-SOUTH") (pin "20") (pinfunction "20_20") (pintype "bidirectional"))
    )
    (net (code "192") (name "S03_N") (class "Default")
      (node (ref "X-SOUTH") (pin "23") (pinfunction "23_23") (pintype "bidirectional"))
    )
    (net (code "193") (name "S03_P") (class "Default")
      (node (ref "X-SOUTH") (pin "21") (pinfunction "21_21") (pintype "bidirectional"))
    )
    (net (code "194") (name "S05_N") (class "Default")
      (node (ref "X-SOUTH") (pin "29") (pinfunction "29_29") (pintype "bidirectional"))
    )
    (net (code "195") (name "S05_P") (class "Default")
      (node (ref "X-SOUTH") (pin "27") (pinfunction "27_27") (pintype "bidirectional"))
    )
    (net (code "196") (name "S38_N") (class "Default")
      (node (ref "X-SOUTH") (pin "130") (pinfunction "130_130") (pintype "bidirectional"))
    )
    (net (code "197") (name "S38_P") (class "Default")
      (node (ref "X-SOUTH") (pin "128") (pinfunction "128_128") (pintype "bidirectional"))
    )
    (net (code "198") (name "S39_N") (class "Default")
      (node (ref "X-SOUTH") (pin "131") (pinfunction "131_131") (pintype "bidirectional"))
    )
    (net (code "199") (name "S39_P") (class "Default")
      (node (ref "X-SOUTH") (pin "129") (pinfunction "129_129") (pintype "bidirectional"))
    )
    (net (code "200") (name "SYS_RES_N") (class "Default")
      (node (ref "X-EAST") (pin "22") (pinfunction "22_22") (pintype "bidirectional"))
      (node (ref "X-NORTH") (pin "125") (pinfunction "125_125") (pintype "bidirectional"))
    )
    (net (code "201") (name "S_CHK_EN") (class "Default")
      (node (ref "X-EAST") (pin "94") (pinfunction "94_94") (pintype "bidirectional"))
      (node (ref "X-SOUTH") (pin "8") (pinfunction "8_8") (pintype "bidirectional"))
    )
    (net (code "202") (name "S_CHK_V") (class "Default")
      (node (ref "X-EAST") (pin "92") (pinfunction "92_92") (pintype "bidirectional"))
      (node (ref "X-SOUTH") (pin "10") (pinfunction "10_10") (pintype "bidirectional"))
    )
    (net (code "203") (name "S_I2C_EN") (class "Default")
      (node (ref "X-SOUTH") (pin "137") (pinfunction "137_137") (pintype "bidirectional"))
      (node (ref "X-WEST") (pin "7") (pinfunction "7_7") (pintype "bidirectional"))
    )
    (net (code "204") (name "S_I2C_V") (class "Default")
      (node (ref "X-SOUTH") (pin "135") (pinfunction "135_135") (pintype "bidirectional"))
      (node (ref "X-WEST") (pin "9") (pinfunction "9_9") (pintype "bidirectional"))
    )
    (net (code "205") (name "S_SCK") (class "Default")
      (node (ref "X-SOUTH") (pin "144") (pinfunction "144_144") (pintype "bidirectional"))
      (node (ref "X-WEST") (pin "2") (pinfunction "2_2") (pintype "bidirectional"))
    )
    (net (code "206") (name "S_SCL") (class "Default")
      (node (ref "X-SOUTH") (pin "143") (pinfunction "143_143") (pintype "bidirectional"))
      (node (ref "X-WEST") (pin "1") (pinfunction "1_1") (pintype "bidirectional"))
    )
    (net (code "207") (name "S_SDA") (class "Default")
      (node (ref "X-SOUTH") (pin "141") (pinfunction "141_141") (pintype "bidirectional"))
      (node (ref "X-WEST") (pin "3") (pinfunction "3_3") (pintype "bidirectional"))
    )
    (net (code "208") (name "S_SDI") (class "Default")
      (node (ref "X-SOUTH") (pin "140") (pinfunction "140_140") (pintype "bidirectional"))
      (node (ref "X-WEST") (pin "6") (pinfunction "6_6") (pintype "bidirectional"))
    )
    (net (code "209") (name "S_SDO") (class "Default")
      (node (ref "X-SOUTH") (pin "142") (pinfunction "142_142") (pintype "bidirectional"))
      (node (ref "X-WEST") (pin "4") (pinfunction "4_4") (pintype "bidirectional"))
    )
    (net (code "210") (name "S_SPI_EN") (class "Default")
      (node (ref "X-SOUTH") (pin "136") (pinfunction "136_136") (pintype "bidirectional"))
      (node (ref "X-WEST") (pin "8") (pinfunction "8_8") (pintype "bidirectional"))
    )
    (net (code "211") (name "S_SPI_V") (class "Default")
      (node (ref "X-SOUTH") (pin "134") (pinfunction "134_134") (pintype "bidirectional"))
      (node (ref "X-WEST") (pin "10") (pinfunction "10_10") (pintype "bidirectional"))
    )
    (net (code "212") (name "S_VE") (class "Default")
      (node (ref "C7") (pin "1") (pinfunction "1_1") (pintype "passive"))
      (node (ref "SE") (pin "1") (pinfunction "1_1") (pintype "passive"))
      (node (ref "X-SOUTH") (pin "13") (pinfunction "13_13") (pintype "bidirectional"))
      (node (ref "X-SOUTH") (pin "19") (pinfunction "19_19") (pintype "bidirectional"))
      (node (ref "X-SOUTH") (pin "31") (pinfunction "31_31") (pintype "bidirectional"))
      (node (ref "X-SOUTH") (pin "37") (pinfunction "37_37") (pintype "bidirectional"))
    )
    (net (code "213") (name "S_VE_CV") (class "Default")
      (node (ref "X-EAST") (pin "100") (pinfunction "100_100") (pintype "bidirectional"))
      (node (ref "X-SOUTH") (pin "2") (pinfunction "2_2") (pintype "bidirectional"))
    )
    (net (code "214") (name "S_VE_OV") (class "Default")
      (node (ref "X-EAST") (pin "99") (pinfunction "99_99") (pintype "bidirectional"))
      (node (ref "X-SOUTH") (pin "1") (pinfunction "1_1") (pintype "bidirectional"))
    )
    (net (code "215") (name "S_VE_RS") (class "Default")
      (node (ref "X-EAST") (pin "84") (pinfunction "84_84") (pintype "bidirectional"))
      (node (ref "X-SOUTH") (pin "25") (pinfunction "25_25") (pintype "bidirectional"))
    )
    (net (code "216") (name "S_VE_UV") (class "Default")
      (node (ref "X-EAST") (pin "89") (pinfunction "89_89") (pintype "bidirectional"))
      (node (ref "X-SOUTH") (pin "7") (pinfunction "7_7") (pintype "bidirectional"))
    )
    (net (code "217") (name "S_VS") (class "Default")
      (node (ref "C6") (pin "1") (pinfunction "1_1") (pintype "passive"))
      (node (ref "SW") (pin "1") (pinfunction "1_1") (pintype "passive"))
      (node (ref "X-SOUTH") (pin "49") (pinfunction "49_49") (pintype "bidirectional"))
      (node (ref "X-SOUTH") (pin "55") (pinfunction "55_55") (pintype "bidirectional"))
      (node (ref "X-SOUTH") (pin "61") (pinfunction "61_61") (pintype "bidirectional"))
      (node (ref "X-SOUTH") (pin "67") (pinfunction "67_67") (pintype "bidirectional"))
      (node (ref "X-SOUTH") (pin "79") (pinfunction "79_79") (pintype "bidirectional"))
      (node (ref "X-SOUTH") (pin "85") (pinfunction "85_85") (pintype "bidirectional"))
      (node (ref "X-SOUTH") (pin "91") (pinfunction "91_91") (pintype "bidirectional"))
      (node (ref "X-SOUTH") (pin "97") (pinfunction "97_97") (pintype "bidirectional"))
    )
    (net (code "218") (name "S_VS_CV") (class "Default")
      (node (ref "X-EAST") (pin "98") (pinfunction "98_98") (pintype "bidirectional"))
      (node (ref "X-SOUTH") (pin "4") (pinfunction "4_4") (pintype "bidirectional"))
    )
    (net (code "219") (name "S_VS_OV") (class "Default")
      (node (ref "X-EAST") (pin "97") (pinfunction "97_97") (pintype "bidirectional"))
      (node (ref "X-SOUTH") (pin "3") (pinfunction "3_3") (pintype "bidirectional"))
    )
    (net (code "220") (name "S_VS_RS") (class "Default")
      (node (ref "X-EAST") (pin "86") (pinfunction "86_86") (pintype "bidirectional"))
      (node (ref "X-SOUTH") (pin "73") (pinfunction "73_73") (pintype "bidirectional"))
    )
    (net (code "221") (name "S_VS_UV") (class "Default")
      (node (ref "X-EAST") (pin "87") (pinfunction "87_87") (pintype "bidirectional"))
      (node (ref "X-SOUTH") (pin "9") (pinfunction "9_9") (pintype "bidirectional"))
    )
    (net (code "222") (name "S_VW") (class "Default")
      (node (ref "C2") (pin "1") (pinfunction "1_1") (pintype "passive"))
      (node (ref "SW") (pin "2") (pinfunction "2_2") (pintype "passive"))
      (node (ref "X-SOUTH") (pin "109") (pinfunction "109_109") (pintype "bidirectional"))
      (node (ref "X-SOUTH") (pin "115") (pinfunction "115_115") (pintype "bidirectional"))
      (node (ref "X-SOUTH") (pin "127") (pinfunction "127_127") (pintype "bidirectional"))
      (node (ref "X-SOUTH") (pin "133") (pinfunction "133_133") (pintype "bidirectional"))
    )
    (net (code "223") (name "S_VW_CV") (class "Default")
      (node (ref "X-EAST") (pin "96") (pinfunction "96_96") (pintype "bidirectional"))
      (node (ref "X-SOUTH") (pin "6") (pinfunction "6_6") (pintype "bidirectional"))
    )
    (net (code "224") (name "S_VW_OV") (class "Default")
      (node (ref "X-EAST") (pin "95") (pinfunction "95_95") (pintype "bidirectional"))
      (node (ref "X-SOUTH") (pin "5") (pinfunction "5_5") (pintype "bidirectional"))
    )
    (net (code "225") (name "S_VW_RS") (class "Default")
      (node (ref "X-EAST") (pin "88") (pinfunction "88_88") (pintype "bidirectional"))
      (node (ref "X-SOUTH") (pin "121") (pinfunction "121_121") (pintype "bidirectional"))
    )
    (net (code "226") (name "S_VW_UV") (class "Default")
      (node (ref "X-EAST") (pin "85") (pinfunction "85_85") (pintype "bidirectional"))
      (node (ref "X-SOUTH") (pin "11") (pinfunction "11_11") (pintype "bidirectional"))
    )
    (net (code "227") (name "TCK") (class "Default")
      (node (ref "X-WEST") (pin "12") (pinfunction "12_12") (pintype "bidirectional"))
    )
    (net (code "228") (name "TDI") (class "Default")
      (node (ref "X-WEST") (pin "16") (pinfunction "16_16") (pintype "bidirectional"))
    )
    (net (code "229") (name "TDIG1") (class "Default")
      (node (ref "X-EAST") (pin "18") (pinfunction "18_18") (pintype "bidirectional"))
      (node (ref "X-NORTH") (pin "123") (pinfunction "123_123") (pintype "bidirectional"))
    )
    (net (code "230") (name "TDIG2") (class "Default")
      (node (ref "X-NORTH") (pin "130") (pinfunction "130_130") (pintype "bidirectional"))
    )
    (net (code "231") (name "TDO") (class "Default")
      (node (ref "X-WEST") (pin "18") (pinfunction "18_18") (pintype "bidirectional"))
    )
    (net (code "232") (name "TMS") (class "Default")
      (node (ref "X-WEST") (pin "14") (pinfunction "14_14") (pintype "bidirectional"))
    )
    (net (code "233") (name "TP9") (class "Default")
      (node (ref "X-NORTH") (pin "119") (pinfunction "119_119") (pintype "bidirectional"))
    )
    (net (code "234") (name "T_EXP1") (class "Default")
      (node (ref "X-EAST") (pin "12") (pinfunction "12_12") (pintype "bidirectional"))
      (node (ref "X-NORTH") (pin "131") (pinfunction "131_131") (pintype "bidirectional"))
    )
    (net (code "235") (name "T_EXP2") (class "Default")
      (node (ref "X-EAST") (pin "16") (pinfunction "16_16") (pintype "bidirectional"))
      (node (ref "X-NORTH") (pin "117") (pinfunction "117_117") (pintype "bidirectional"))
    )
    (net (code "236") (name "W_EN") (class "Default")
      (node (ref "X-WEST") (pin "19") (pinfunction "19_19") (pintype "bidirectional"))
    )
    (net (code "237") (name "W_I2C_EN") (class "Default")
      (node (ref "X-WEST") (pin "13") (pinfunction "13_13") (pintype "bidirectional"))
    )
    (net (code "238") (name "W_I2C_V") (class "Default")
      (node (ref "X-WEST") (pin "11") (pinfunction "11_11") (pintype "bidirectional"))
    )
    (net (code "239") (name "W_SCL") (class "Default")
      (node (ref "X-WEST") (pin "15") (pinfunction "15_15") (pintype "bidirectional"))
    )
    (net (code "240") (name "W_SDA") (class "Default")
      (node (ref "X-WEST") (pin "17") (pinfunction "17_17") (pintype "bidirectional"))
    )
    (net (code "241") (name "W_VW") (class "Default")
      (node (ref "C8") (pin "1") (pinfunction "1_1") (pintype "passive"))
      (node (ref "NW") (pin "2") (pinfunction "2_2") (pintype "passive"))
    )
    (net (code "242") (name "W_VW_CV") (class "Default")
      (node (ref "X-WEST") (pin "90") (pinfunction "90_90") (pintype "bidirectional"))
    )
    (net (code "243") (name "W_VW_OV") (class "Default")
      (node (ref "X-WEST") (pin "93") (pinfunction "93_93") (pintype "bidirectional"))
    )
    (net (code "244") (name "W_VW_UV") (class "Default")
      (node (ref "X-WEST") (pin "91") (pinfunction "91_91") (pintype "bidirectional"))
    )
    (net (code "245") (name "unconnected-(X-EAST-PadM1)") (class "Default")
      (node (ref "X-EAST") (pin "M1") (pinfunction "M1_M1") (pintype "bidirectional"))
    )
    (net (code "246") (name "unconnected-(X-EAST-PadM2)") (class "Default")
      (node (ref "X-EAST") (pin "M2") (pinfunction "M2_M2") (pintype "bidirectional"))
    )
    (net (code "247") (name "unconnected-(X-NORTH-PadM1)") (class "Default")
      (node (ref "X-NORTH") (pin "M1") (pinfunction "M1_M1") (pintype "bidirectional"))
    )
    (net (code "248") (name "unconnected-(X-NORTH-PadM2)") (class "Default")
      (node (ref "X-NORTH") (pin "M2") (pinfunction "M2_M2") (pintype "bidirectional"))
    )
    (net (code "249") (name "unconnected-(X-SOUTH-PadM1)") (class "Default")
      (node (ref "X-SOUTH") (pin "M1") (pinfunction "M1_M1") (pintype "bidirectional"))
    )
    (net (code "250") (name "unconnected-(X-SOUTH-PadM2)") (class "Default")
      (node (ref "X-SOUTH") (pin "M2") (pinfunction "M2_M2") (pintype "bidirectional"))
    )
    (net (code "251") (name "unconnected-(X-WEST-PadM1)") (class "Default")
      (node (ref "X-WEST") (pin "M1") (pinfunction "M1_M1") (pintype "bidirectional"))
    )
    (net (code "252") (name "unconnected-(X-WEST-PadM2)") (class "Default")
      (node (ref "X-WEST") (pin "M2") (pinfunction "M2_M2") (pintype "bidirectional"))
    )
  )
)
